# eagle-a31301-breakout-board.net
KiCad netlist of a schematic drawn in EAGLE
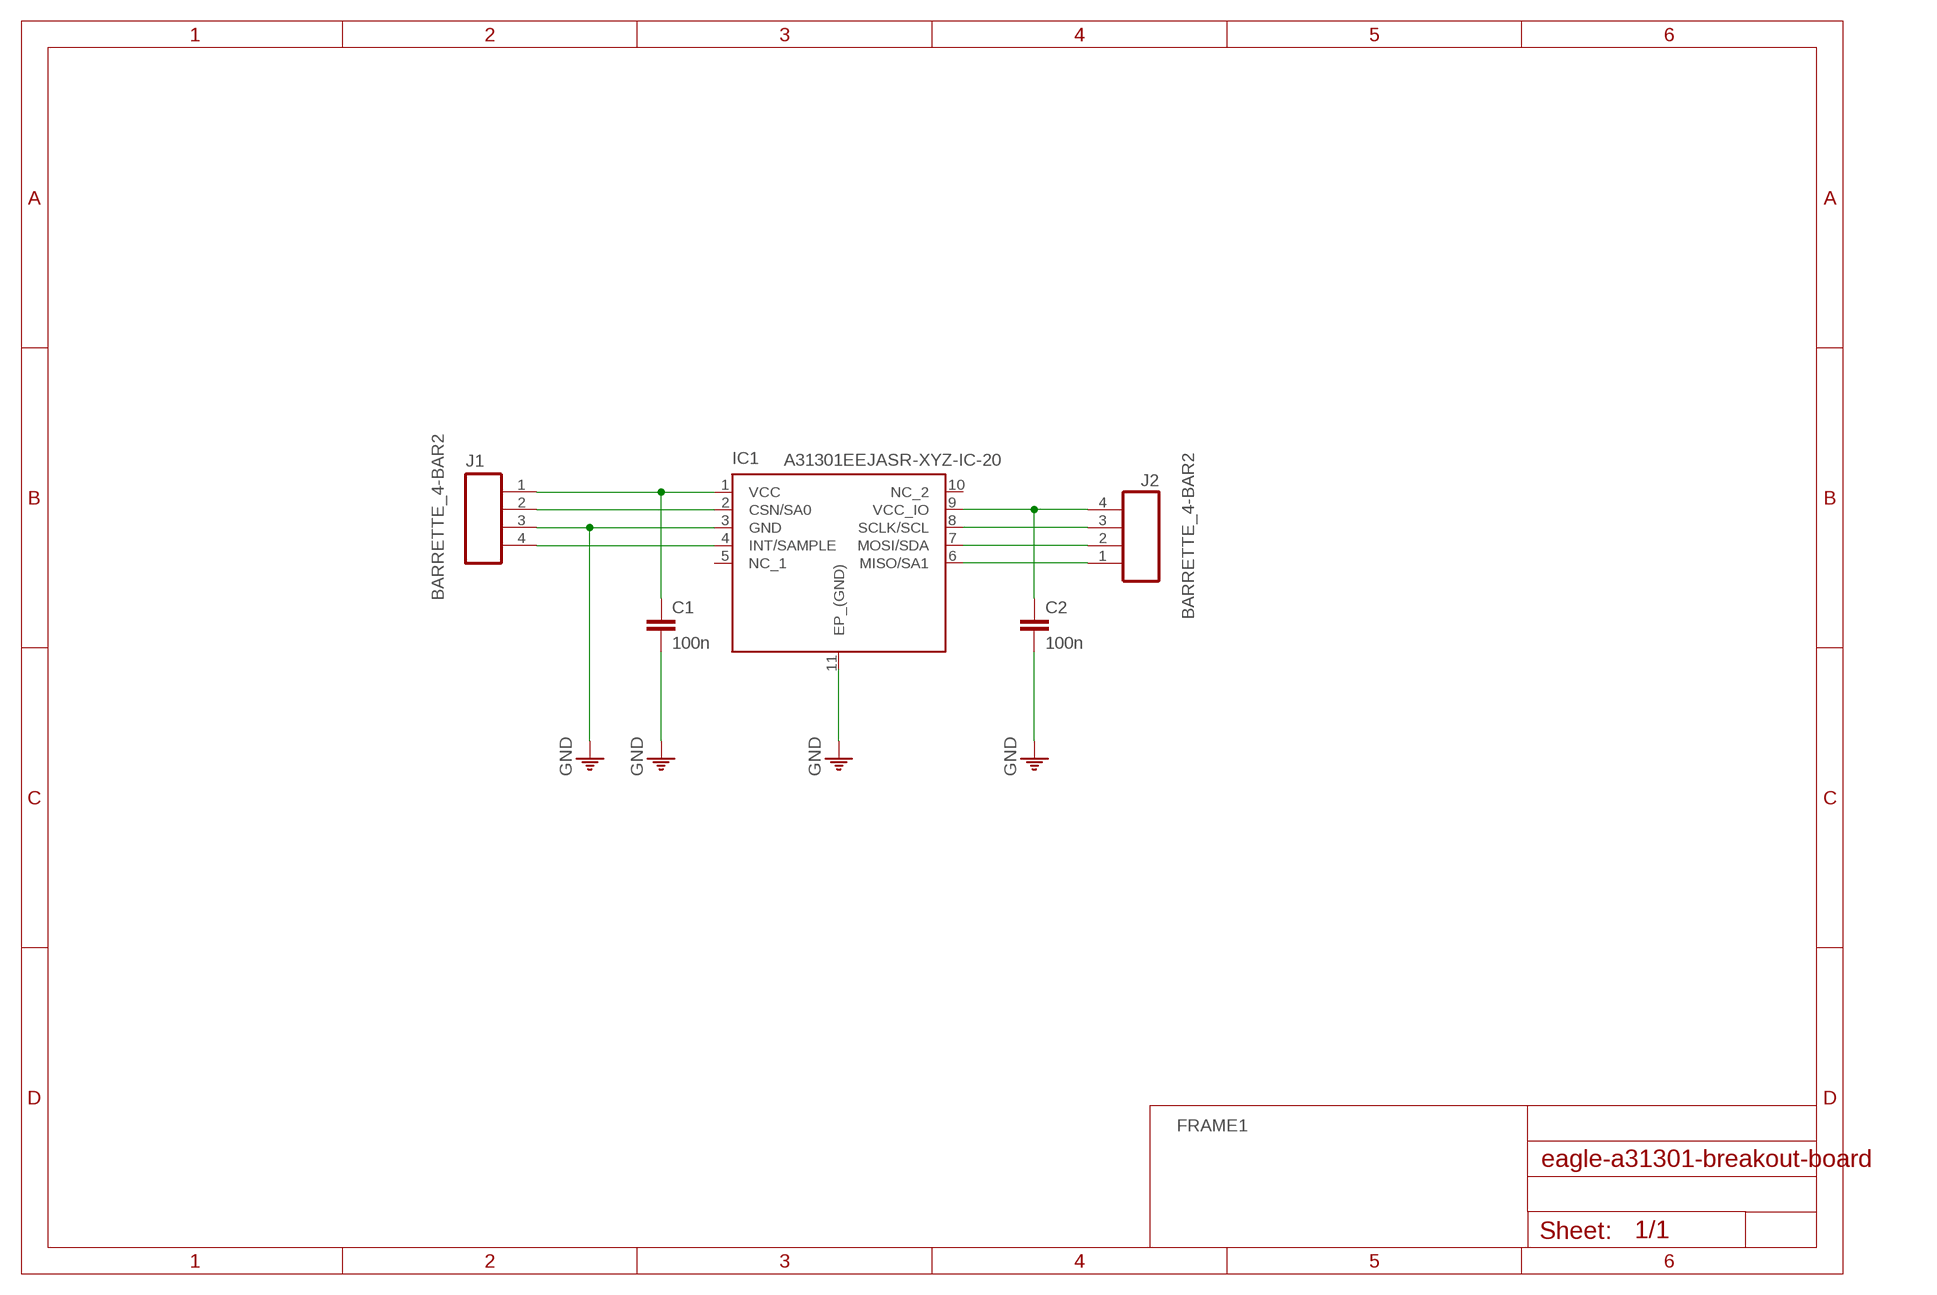
[diagram p0: schematic, sheet 1]

(export (version "E")
  (design (tool "Eeschema 10.0.6"))
  (components
    (comp (ref "C1")
      (value "100n")
      (footprint "eagle-import:CCMS1206")
      (libsource (lib "eagle-import") (part "C-CMS1206"))
    )
    (comp (ref "C2")
      (value "100n")
      (footprint "eagle-import:CCMS1206")
      (libsource (lib "eagle-import") (part "C-CMS1206"))
    )
    (comp (ref "IC1")
      (value "A31301EEJASR-XYZ-IC-20")
      (footprint "eagle-import:DFN-10")
      (fields (field (name "MOUSER_PART_NUMBER") "250-A31301EEJASRIC20"))
      (libsource (lib "eagle-import") (part "A31301EEJASR-XYZ-IC-20"))
    )
    (comp (ref "J1")
      (value "BARRETTE_4-BAR2")
      (footprint "eagle-import:FE04")
      (libsource (lib "eagle-import") (part "BARRETTE_4-BAR2"))
    )
    (comp (ref "J2")
      (value "BARRETTE_4-BAR2")
      (footprint "eagle-import:FE04")
      (libsource (lib "eagle-import") (part "BARRETTE_4-BAR2"))
    )
  )
  (nets
    (net (code "1") (name "GND") (class "Default")
      (node (ref "C1") (pin "2") (pinfunction "2_2") (pintype "passive"))
      (node (ref "C2") (pin "2") (pinfunction "2_2") (pintype "passive"))
      (node (ref "IC1") (pin "11") (pinfunction "EP_(GND)_11") (pintype "bidirectional"))
      (node (ref "IC1") (pin "3") (pinfunction "GND_3") (pintype "bidirectional"))
      (node (ref "J1") (pin "3") (pinfunction "3_3") (pintype "passive"))
    )
    (net (code "2") (name "Net-(IC1-CSN{slash}SA0)") (class "Default")
      (node (ref "IC1") (pin "2") (pinfunction "CSN/SA0_2") (pintype "bidirectional"))
      (node (ref "J1") (pin "2") (pinfunction "2_2") (pintype "passive"))
    )
    (net (code "3") (name "Net-(IC1-INT{slash}SAMPLE)") (class "Default")
      (node (ref "IC1") (pin "4") (pinfunction "INT/SAMPLE_4") (pintype "bidirectional"))
      (node (ref "J1") (pin "4") (pinfunction "4_4") (pintype "passive"))
    )
    (net (code "4") (name "Net-(IC1-MISO{slash}SA1)") (class "Default")
      (node (ref "IC1") (pin "6") (pinfunction "MISO/SA1_6") (pintype "bidirectional"))
      (node (ref "J2") (pin "1") (pinfunction "1_1") (pintype "passive"))
    )
    (net (code "5") (name "Net-(IC1-MOSI{slash}SDA)") (class "Default")
      (node (ref "IC1") (pin "7") (pinfunction "MOSI/SDA_7") (pintype "bidirectional"))
      (node (ref "J2") (pin "2") (pinfunction "2_2") (pintype "passive"))
    )
    (net (code "6") (name "Net-(IC1-SCLK{slash}SCL)") (class "Default")
      (node (ref "IC1") (pin "8") (pinfunction "SCLK/SCL_8") (pintype "bidirectional"))
      (node (ref "J2") (pin "3") (pinfunction "3_3") (pintype "passive"))
    )
    (net (code "7") (name "Net-(IC1-VCC)") (class "Default")
      (node (ref "C1") (pin "1") (pinfunction "1_1") (pintype "passive"))
      (node (ref "IC1") (pin "1") (pinfunction "VCC_1") (pintype "bidirectional"))
      (node (ref "J1") (pin "1") (pinfunction "1_1") (pintype "passive"))
    )
    (net (code "8") (name "Net-(IC1-VCC_IO)") (class "Default")
      (node (ref "C2") (pin "1") (pinfunction "1_1") (pintype "passive"))
      (node (ref "IC1") (pin "9") (pinfunction "VCC_IO_9") (pintype "bidirectional"))
      (node (ref "J2") (pin "4") (pinfunction "4_4") (pintype "passive"))
    )
    (net (code "9") (name "unconnected-(IC1-NC_1-Pad5)") (class "Default")
      (node (ref "IC1") (pin "5") (pinfunction "NC_1_5") (pintype "bidirectional"))
    )
    (net (code "10") (name "unconnected-(IC1-NC_2-Pad10)") (class "Default")
      (node (ref "IC1") (pin "10") (pinfunction "NC_2_10") (pintype "bidirectional"))
    )
  )
)
